# ps2.net
KiCad netlist of a schematic drawn in EAGLE
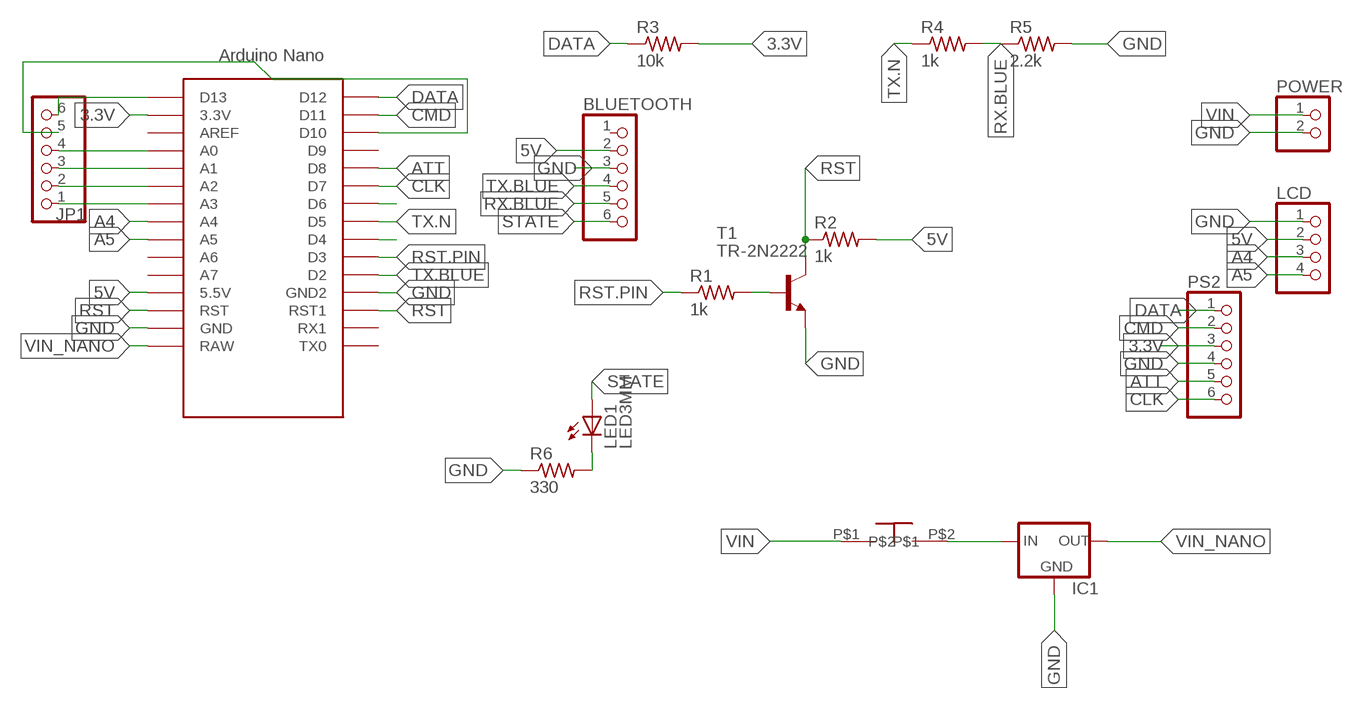
[diagram p0: schematic, sheet 1]

(export (version "E")
  (design (tool "Eeschema 10.0.6"))
  (components
    (comp (ref "BLUETOOTH")
      (value "PINHD-1X6")
      (footprint "eagle-import:1X06")
      (libsource (lib "eagle-import") (part "PINHD-1X6"))
    )
    (comp (ref "IC1")
      (value "78XXS")
      (footprint "eagle-import:78XXS")
      (libsource (lib "eagle-import") (part "78XXS"))
    )
    (comp (ref "JP1")
      (value "PINHD-1X6")
      (footprint "eagle-import:1X06")
      (libsource (lib "eagle-import") (part "PINHD-1X6"))
    )
    (comp (ref "LCD")
      (value "PINHD-1X4")
      (footprint "eagle-import:1X04")
      (libsource (lib "eagle-import") (part "PINHD-1X4"))
    )
    (comp (ref "LED1")
      (value "LED3MM")
      (footprint "eagle-import:LED3MM")
      (libsource (lib "eagle-import") (part "LED3MM"))
    )
    (comp (ref "POWER")
      (value "PINHD-1X2")
      (footprint "eagle-import:1X02")
      (libsource (lib "eagle-import") (part "PINHD-1X2"))
    )
    (comp (ref "PS2")
      (value "PINHD-1X6")
      (footprint "eagle-import:1X06")
      (libsource (lib "eagle-import") (part "PINHD-1X6"))
    )
    (comp (ref "R1")
      (value "1k")
      (footprint "eagle-import:0204_5")
      (libsource (lib "eagle-import") (part "RES-5"))
    )
    (comp (ref "R2")
      (value "1k")
      (footprint "eagle-import:0204_5")
      (libsource (lib "eagle-import") (part "RES-5"))
    )
    (comp (ref "R3")
      (value "10k")
      (footprint "eagle-import:0204_5")
      (libsource (lib "eagle-import") (part "RES-5"))
    )
    (comp (ref "R4")
      (value "1k")
      (footprint "eagle-import:0204_5")
      (libsource (lib "eagle-import") (part "RES-5"))
    )
    (comp (ref "R5")
      (value "2.2k")
      (footprint "eagle-import:0204_5")
      (libsource (lib "eagle-import") (part "RES-5"))
    )
    (comp (ref "R6")
      (value "330")
      (footprint "eagle-import:0204_5")
      (libsource (lib "eagle-import") (part "RES-5"))
    )
    (comp (ref "T1")
      (value "TR-2N2222")
      (footprint "eagle-import:TO18")
      (libsource (lib "eagle-import") (part "TR-2N2222"))
    )
    (comp (ref "U$1")
      (value "ARDUINO_NANO")
      (footprint "eagle-import:NANO")
      (libsource (lib "eagle-import") (part "ARDUINO_NANO"))
    )
    (comp (ref "U$2")
      (value "SWITCH_2")
      (footprint "eagle-import:ON_OFF")
      (libsource (lib "eagle-import") (part "SWITCH_2"))
    )
  )
  (nets
    (net (code "1") (name "3.3V") (class "Default")
      (node (ref "PS2") (pin "3") (pinfunction "3_3") (pintype "passive"))
      (node (ref "R3") (pin "2") (pinfunction "2_2") (pintype "passive"))
      (node (ref "U$1") (pin "3.3V") (pinfunction "3.3V_3.3V") (pintype "bidirectional"))
    )
    (net (code "2") (name "5V") (class "Default")
      (node (ref "BLUETOOTH") (pin "2") (pinfunction "2_2") (pintype "passive"))
      (node (ref "LCD") (pin "2") (pinfunction "2_2") (pintype "passive"))
      (node (ref "R2") (pin "2") (pinfunction "2_2") (pintype "passive"))
      (node (ref "U$1") (pin "5V") (pinfunction "5.5V_5V") (pintype "bidirectional"))
    )
    (net (code "3") (name "A4") (class "Default")
      (node (ref "LCD") (pin "3") (pinfunction "3_3") (pintype "passive"))
      (node (ref "U$1") (pin "A4") (pinfunction "A4_A4") (pintype "bidirectional"))
    )
    (net (code "4") (name "A5") (class "Default")
      (node (ref "LCD") (pin "4") (pinfunction "4_4") (pintype "passive"))
      (node (ref "U$1") (pin "A5") (pinfunction "A5_A5") (pintype "bidirectional"))
    )
    (net (code "5") (name "ATT") (class "Default")
      (node (ref "PS2") (pin "5") (pinfunction "5_5") (pintype "passive"))
      (node (ref "U$1") (pin "D8") (pinfunction "D8_D8") (pintype "bidirectional"))
    )
    (net (code "6") (name "CLK") (class "Default")
      (node (ref "PS2") (pin "6") (pinfunction "6_6") (pintype "passive"))
      (node (ref "U$1") (pin "D7") (pinfunction "D7_D7") (pintype "bidirectional"))
    )
    (net (code "7") (name "CMD") (class "Default")
      (node (ref "PS2") (pin "2") (pinfunction "2_2") (pintype "passive"))
      (node (ref "U$1") (pin "D11") (pinfunction "D11_D11") (pintype "bidirectional"))
    )
    (net (code "8") (name "DATA") (class "Default")
      (node (ref "PS2") (pin "1") (pinfunction "1_1") (pintype "passive"))
      (node (ref "R3") (pin "1") (pinfunction "1_1") (pintype "passive"))
      (node (ref "U$1") (pin "D12") (pinfunction "D12_D12") (pintype "bidirectional"))
    )
    (net (code "9") (name "GND") (class "Default")
      (node (ref "BLUETOOTH") (pin "3") (pinfunction "3_3") (pintype "passive"))
      (node (ref "IC1") (pin "GND") (pinfunction "GND_GND") (pintype "input"))
      (node (ref "LCD") (pin "1") (pinfunction "1_1") (pintype "passive"))
      (node (ref "POWER") (pin "2") (pinfunction "2_2") (pintype "passive"))
      (node (ref "PS2") (pin "4") (pinfunction "4_4") (pintype "passive"))
      (node (ref "R5") (pin "2") (pinfunction "2_2") (pintype "passive"))
      (node (ref "R6") (pin "1") (pinfunction "1_1") (pintype "passive"))
      (node (ref "T1") (pin "1") (pinfunction "E_1") (pintype "passive"))
      (node (ref "U$1") (pin "GND") (pinfunction "GND_GND") (pintype "bidirectional"))
      (node (ref "U$1") (pin "GND1") (pinfunction "GND2_GND1") (pintype "bidirectional"))
    )
    (net (code "10") (name "Net-(IC1-PadIN)") (class "Default")
      (node (ref "IC1") (pin "IN") (pinfunction "IN_IN") (pintype "input"))
      (node (ref "U$2") (pin "P$2") (pinfunction "P$2_P$2") (pintype "bidirectional"))
    )
    (net (code "11") (name "Net-(JP1-Pad1)") (class "Default")
      (node (ref "JP1") (pin "1") (pinfunction "1_1") (pintype "passive"))
      (node (ref "U$1") (pin "A3") (pinfunction "A3_A3") (pintype "bidirectional"))
    )
    (net (code "12") (name "Net-(JP1-Pad2)") (class "Default")
      (node (ref "JP1") (pin "2") (pinfunction "2_2") (pintype "passive"))
      (node (ref "U$1") (pin "A2") (pinfunction "A2_A2") (pintype "bidirectional"))
    )
    (net (code "13") (name "Net-(JP1-Pad3)") (class "Default")
      (node (ref "JP1") (pin "3") (pinfunction "3_3") (pintype "passive"))
      (node (ref "U$1") (pin "A1") (pinfunction "A1_A1") (pintype "bidirectional"))
    )
    (net (code "14") (name "Net-(JP1-Pad4)") (class "Default")
      (node (ref "JP1") (pin "4") (pinfunction "4_4") (pintype "passive"))
      (node (ref "U$1") (pin "A0") (pinfunction "A0_A0") (pintype "bidirectional"))
    )
    (net (code "15") (name "Net-(JP1-Pad5)") (class "Default")
      (node (ref "JP1") (pin "5") (pinfunction "5_5") (pintype "passive"))
      (node (ref "U$1") (pin "D10") (pinfunction "D10_D10") (pintype "bidirectional"))
    )
    (net (code "16") (name "Net-(JP1-Pad6)") (class "Default")
      (node (ref "JP1") (pin "6") (pinfunction "6_6") (pintype "passive"))
      (node (ref "U$1") (pin "D13") (pinfunction "D13_D13") (pintype "bidirectional"))
    )
    (net (code "17") (name "Net-(LED1-C)") (class "Default")
      (node (ref "LED1") (pin "K") (pinfunction "C_K") (pintype "passive"))
      (node (ref "R6") (pin "2") (pinfunction "2_2") (pintype "passive"))
    )
    (net (code "18") (name "Net-(T1-B)") (class "Default")
      (node (ref "R1") (pin "2") (pinfunction "2_2") (pintype "passive"))
      (node (ref "T1") (pin "2") (pinfunction "B_2") (pintype "passive"))
    )
    (net (code "19") (name "RST") (class "Default")
      (node (ref "R2") (pin "1") (pinfunction "1_1") (pintype "passive"))
      (node (ref "T1") (pin "3") (pinfunction "C_3") (pintype "passive"))
      (node (ref "U$1") (pin "RST") (pinfunction "RST_RST") (pintype "bidirectional"))
      (node (ref "U$1") (pin "RST1") (pinfunction "RST1_RST1") (pintype "bidirectional"))
    )
    (net (code "20") (name "RST.PIN") (class "Default")
      (node (ref "R1") (pin "1") (pinfunction "1_1") (pintype "passive"))
      (node (ref "U$1") (pin "D3") (pinfunction "D3_D3") (pintype "bidirectional"))
    )
    (net (code "21") (name "RX.BLUE") (class "Default")
      (node (ref "BLUETOOTH") (pin "5") (pinfunction "5_5") (pintype "passive"))
      (node (ref "R4") (pin "2") (pinfunction "2_2") (pintype "passive"))
      (node (ref "R5") (pin "1") (pinfunction "1_1") (pintype "passive"))
    )
    (net (code "22") (name "STATE") (class "Default")
      (node (ref "BLUETOOTH") (pin "6") (pinfunction "6_6") (pintype "passive"))
      (node (ref "LED1") (pin "A") (pinfunction "A_A") (pintype "passive"))
    )
    (net (code "23") (name "TX.BLUE") (class "Default")
      (node (ref "BLUETOOTH") (pin "4") (pinfunction "4_4") (pintype "passive"))
      (node (ref "U$1") (pin "D2") (pinfunction "D2_D2") (pintype "bidirectional"))
    )
    (net (code "24") (name "TX.N") (class "Default")
      (node (ref "R4") (pin "1") (pinfunction "1_1") (pintype "passive"))
      (node (ref "U$1") (pin "D5") (pinfunction "D5_D5") (pintype "bidirectional"))
    )
    (net (code "25") (name "VIN") (class "Default")
      (node (ref "POWER") (pin "1") (pinfunction "1_1") (pintype "passive"))
      (node (ref "U$2") (pin "P$1") (pinfunction "P$1_P$1") (pintype "bidirectional"))
    )
    (net (code "26") (name "VIN_NANO") (class "Default")
      (node (ref "IC1") (pin "OUT") (pinfunction "OUT_OUT") (pintype "passive"))
      (node (ref "U$1") (pin "RAW") (pinfunction "RAW_RAW") (pintype "bidirectional"))
    )
    (net (code "27") (name "unconnected-(BLUETOOTH-Pad1)") (class "Default")
      (node (ref "BLUETOOTH") (pin "1") (pinfunction "1_1") (pintype "passive"))
    )
    (net (code "28") (name "unconnected-(U$1-PadA6)") (class "Default")
      (node (ref "U$1") (pin "A6") (pinfunction "A6_A6") (pintype "bidirectional"))
    )
    (net (code "29") (name "unconnected-(U$1-PadA7)") (class "Default")
      (node (ref "U$1") (pin "A7") (pinfunction "A7_A7") (pintype "bidirectional"))
    )
    (net (code "30") (name "unconnected-(U$1-PadAREF)") (class "Default")
      (node (ref "U$1") (pin "AREF") (pinfunction "AREF_AREF") (pintype "bidirectional"))
    )
    (net (code "31") (name "unconnected-(U$1-PadD4)") (class "Default")
      (node (ref "U$1") (pin "D4") (pinfunction "D4_D4") (pintype "bidirectional"))
    )
    (net (code "32") (name "unconnected-(U$1-PadD6)") (class "Default")
      (node (ref "U$1") (pin "D6") (pinfunction "D6_D6") (pintype "bidirectional"))
    )
    (net (code "33") (name "unconnected-(U$1-PadD9)") (class "Default")
      (node (ref "U$1") (pin "D9") (pinfunction "D9_D9") (pintype "bidirectional"))
    )
    (net (code "34") (name "unconnected-(U$1-PadRX1)") (class "Default")
      (node (ref "U$1") (pin "RX1") (pinfunction "RX1_RX1") (pintype "bidirectional"))
    )
    (net (code "35") (name "unconnected-(U$1-PadTX0)") (class "Default")
      (node (ref "U$1") (pin "TX0") (pinfunction "TX0_TX0") (pintype "bidirectional"))
    )
  )
)
